# Connectors.net
KiCad netlist of a schematic drawn in Altium Designer
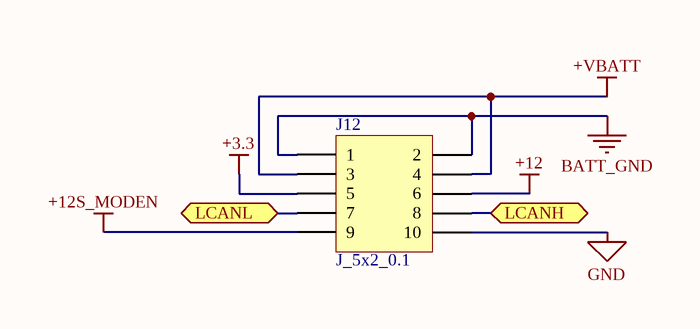
[diagram p0: Connectors.SchDoc]

(export (version "E")
  (design (tool "Eeschema 10.0.6"))
  (components
    (comp (ref "J12")
      (value "J_5x2_0.1")
      (footprint "10PIN_2_.100IN")
      (description "5 x 2 0.1\" Header")
      (libsource (lib "Nutz") (part "J_5x2_0.1"))
    )
  )
  (nets
    (net (code "1") (name "+3.3") (class "Default")
      (node (ref "J12") (pin "5") (pinfunction "5_5") (pintype "passive"))
    )
    (net (code "2") (name "+12") (class "Default")
      (node (ref "J12") (pin "6") (pinfunction "6_6") (pintype "passive"))
    )
    (net (code "3") (name "+12S_MODEN") (class "Default")
      (node (ref "J12") (pin "9") (pinfunction "9_9") (pintype "passive"))
    )
    (net (code "4") (name "+VBATT") (class "Default")
      (node (ref "J12") (pin "3") (pinfunction "3_3") (pintype "passive"))
      (node (ref "J12") (pin "4") (pinfunction "4_4") (pintype "passive"))
    )
    (net (code "5") (name "/LCANH") (class "Default")
      (node (ref "J12") (pin "8") (pinfunction "8_8") (pintype "passive"))
    )
    (net (code "6") (name "/LCANL") (class "Default")
      (node (ref "J12") (pin "7") (pinfunction "7_7") (pintype "passive"))
    )
    (net (code "7") (name "BATT_GND") (class "Default")
      (node (ref "J12") (pin "1") (pinfunction "1_1") (pintype "passive"))
      (node (ref "J12") (pin "2") (pinfunction "2_2") (pintype "passive"))
    )
    (net (code "8") (name "GND") (class "Default")
      (node (ref "J12") (pin "10") (pinfunction "10_10") (pintype "passive"))
    )
  )
)
